# EEZ_AUX_PS_r5B6b.net
KiCad netlist of a schematic drawn in EAGLE
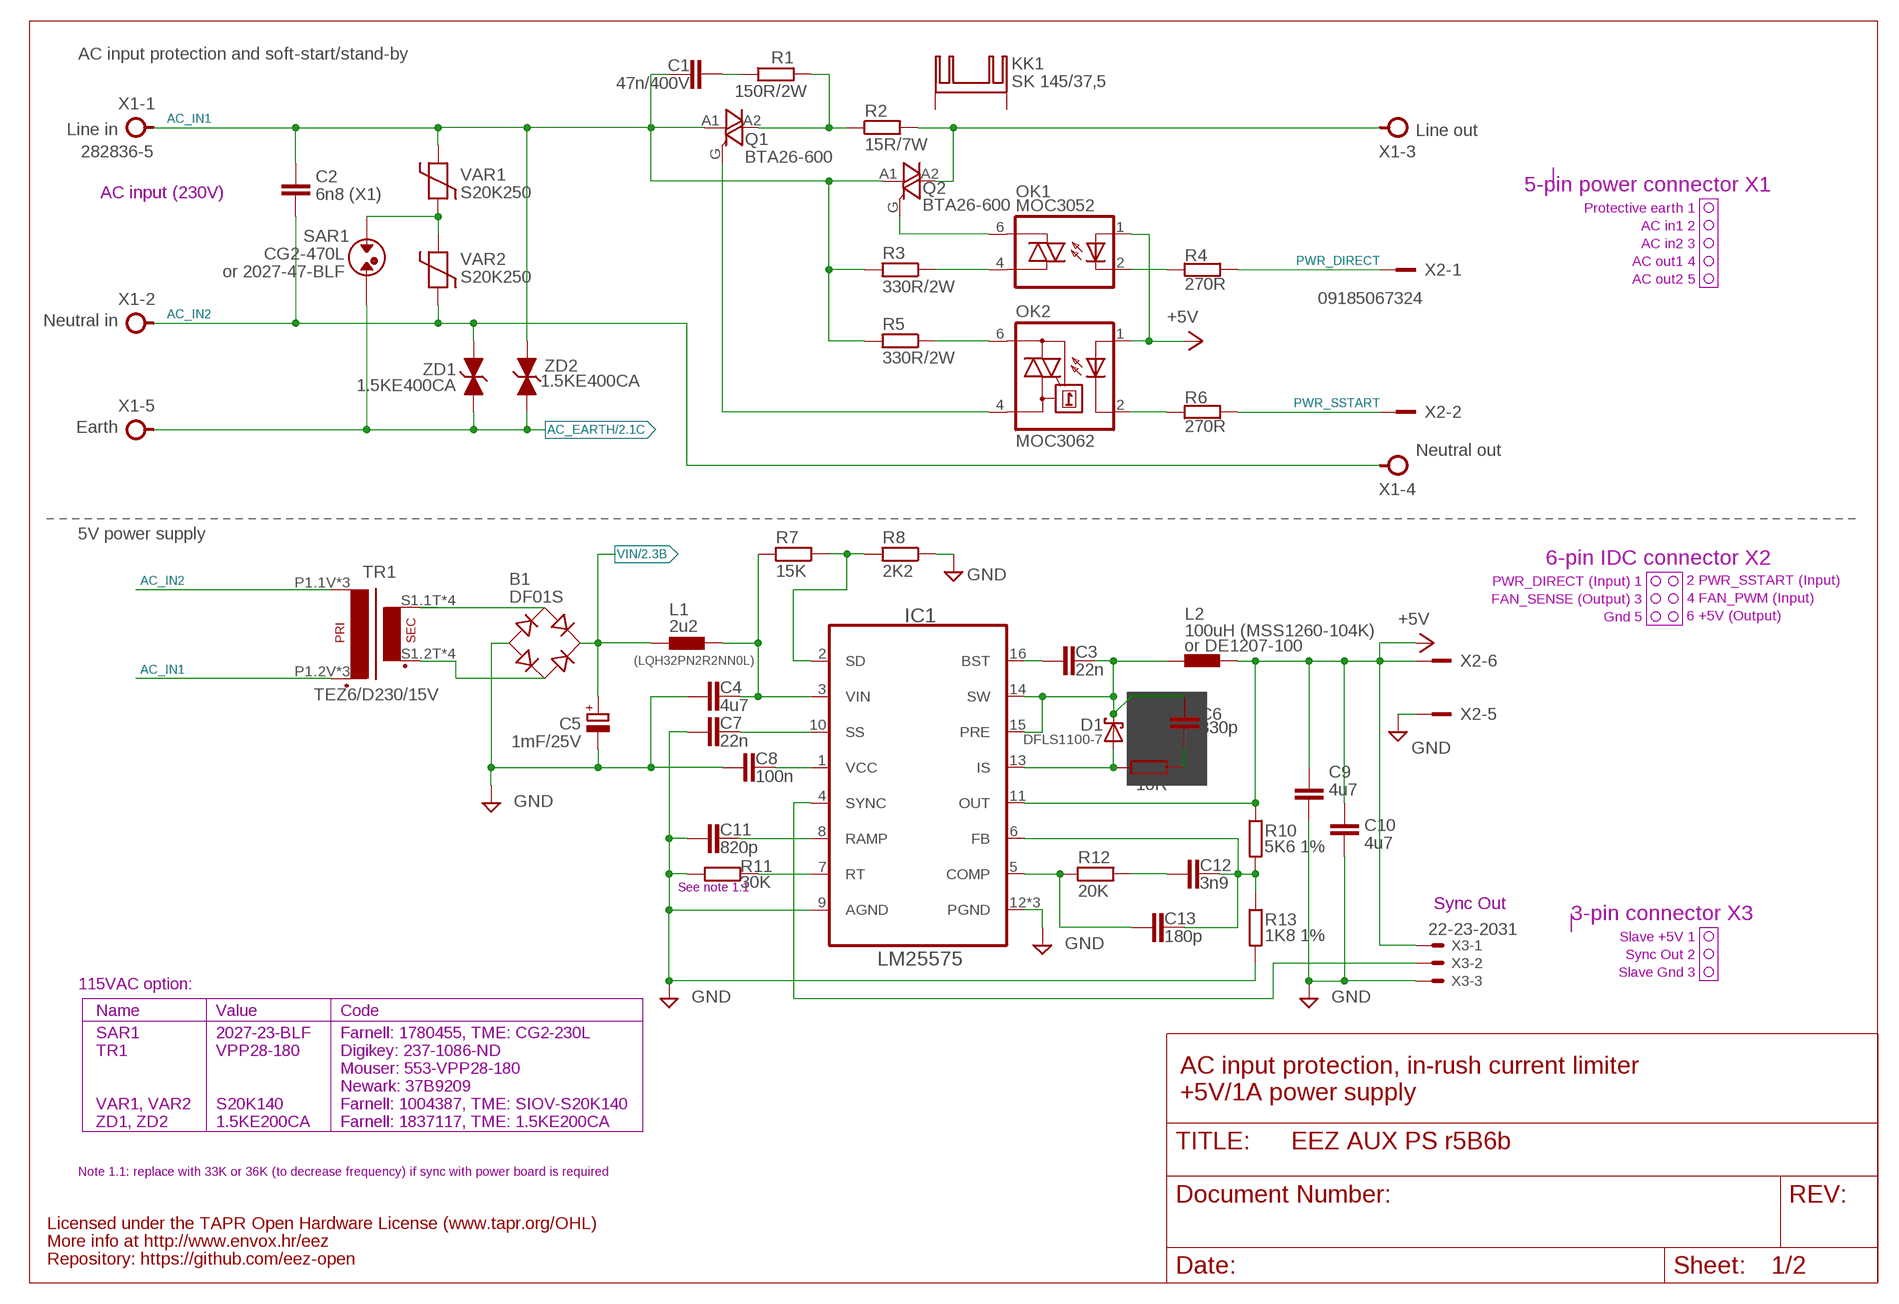
[diagram p0: schematic, sheet 1]
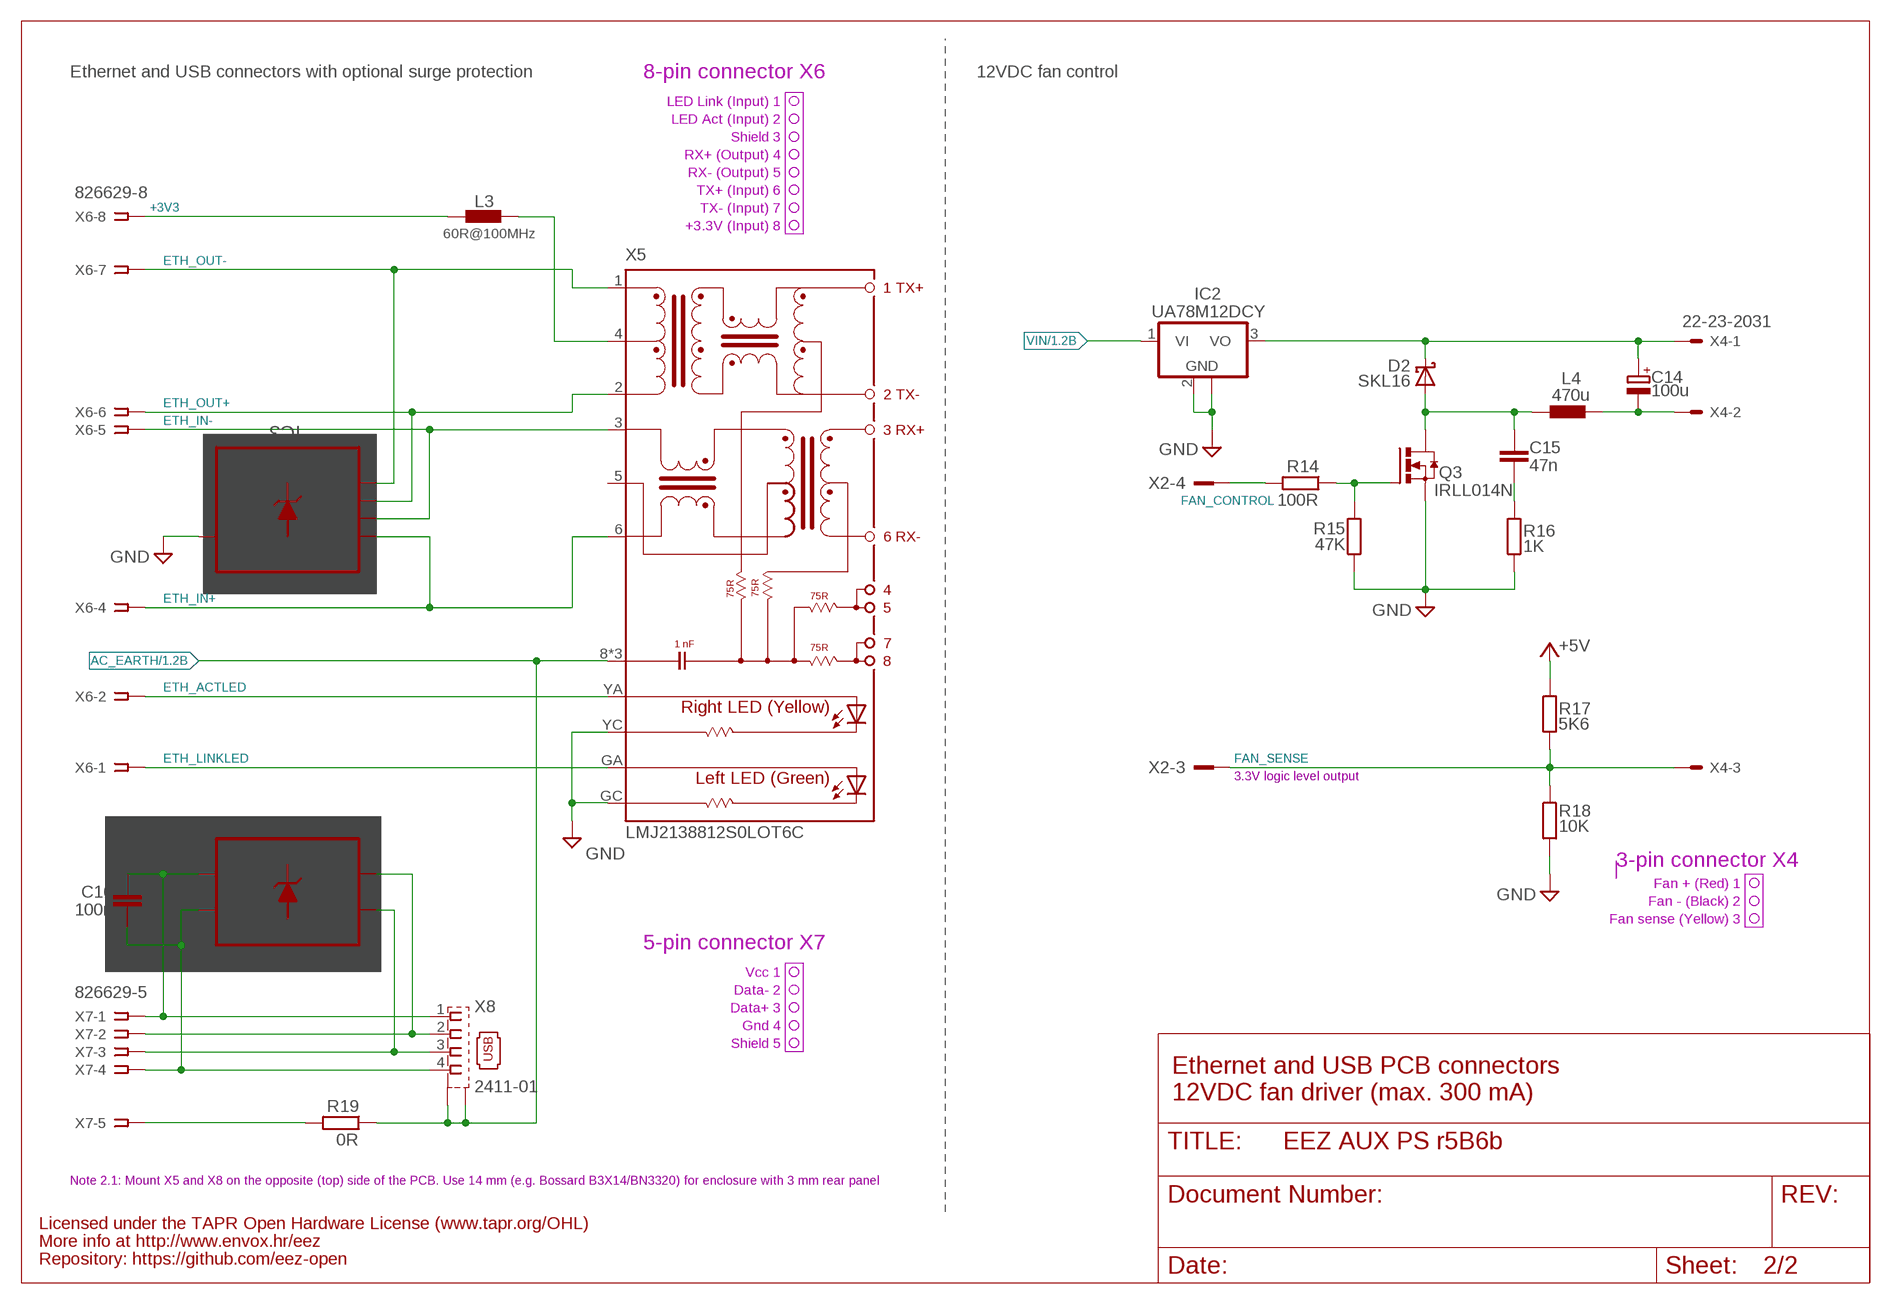
[diagram p1: schematic, sheet 2]

(export (version "E")
  (design (tool "Eeschema 10.0.6"))
  (components
    (comp (ref "C14")
      (value "100u")
      (footprint "eagle-import:CAPAE660X610N")
      (libsource (lib "eagle-import") (part "ECAPPANASONIC_H"))
    )
    (comp (ref "C15")
      (value "47n")
      (footprint "eagle-import:C0805")
      (libsource (lib "eagle-import") (part "C-EUC0805"))
    )
    (comp (ref "C16")
      (value "100n")
      (footprint "eagle-import:C0805")
      (libsource (lib "eagle-import") (part "C-EUC0805"))
    )
    (comp (ref "D2")
      (value "SKL16")
      (footprint "eagle-import:SOD123")
      (libsource (lib "eagle-import") (part "SCHOTTKYSOD123"))
    )
    (comp (ref "IC2")
      (value "UA78M12DCY")
      (footprint "eagle-import:SOT230P700X180-4N")
      (libsource (lib "eagle-import") (part "UA78MDCY"))
    )
    (comp (ref "IC3")
      (value "TPD4E002DRLR")
      (footprint "eagle-import:SOT50P280X60-5N")
      (libsource (lib "eagle-import") (part "TPD4E002DRLR"))
    )
    (comp (ref "IC4")
      (value "TPD2E001DZDR")
      (footprint "eagle-import:SOP192P292X122-4N")
      (libsource (lib "eagle-import") (part "TPD2E001DZDR"))
    )
    (comp (ref "L3")
      (value "60R@100MHz")
      (footprint "eagle-import:BEAD0603")
      (libsource (lib "eagle-import") (part "FERRITE_BEAD0603"))
    )
    (comp (ref "L4")
      (value "470u")
      (footprint "eagle-import:DE0704")
      (libsource (lib "eagle-import") (part "DE0704"))
    )
    (comp (ref "Q3")
      (value "IRLL014N")
      (footprint "eagle-import:SOT223")
      (libsource (lib "eagle-import") (part "N-HEXFET-2D_?-SOT232IRLL014N"))
    )
    (comp (ref "R14")
      (value "100R")
      (footprint "eagle-import:R0805")
      (libsource (lib "eagle-import") (part "R-EU_R0805"))
    )
    (comp (ref "R15")
      (value "47K")
      (footprint "eagle-import:R0805")
      (libsource (lib "eagle-import") (part "R-EU_R0805"))
    )
    (comp (ref "R16")
      (value "1K")
      (footprint "eagle-import:R0805")
      (libsource (lib "eagle-import") (part "R-EU_R0805"))
    )
    (comp (ref "R17")
      (value "5K6")
      (footprint "eagle-import:R0805")
      (libsource (lib "eagle-import") (part "R-EU_R0805"))
    )
    (comp (ref "R18")
      (value "10K")
      (footprint "eagle-import:R0805")
      (libsource (lib "eagle-import") (part "R-EU_R0805"))
    )
    (comp (ref "R19")
      (value "0R")
      (footprint "eagle-import:R0805")
      (libsource (lib "eagle-import") (part "R-EU_R0805"))
    )
    (comp (ref "X2")
      (value "09185067324")
      (footprint "eagle-import:IDC-6PIN")
      (libsource (lib "eagle-import") (part "IDC-6PIN"))
    )
    (comp (ref "X4")
      (value "22-23-2031")
      (footprint "eagle-import:22-23-2031")
      (fields (field (name "MF") "MOLEX"))
      (libsource (lib "eagle-import") (part "22-23-2031"))
    )
    (comp (ref "X5")
      (value "LMJ2138812S0LOT6C")
      (footprint "eagle-import:RJ45-VERT")
      (libsource (lib "eagle-import") (part "RJ45-VERT"))
    )
    (comp (ref "X6")
      (value "826629-8")
      (footprint "eagle-import:SSW-108-02-S-S")
      (fields (field (name "MPN") "SSW-108-02-S-S"))
      (libsource (lib "eagle-import") (part "SSW-108-02-S-S"))
    )
    (comp (ref "X7")
      (value "826629-5")
      (footprint "eagle-import:SSW-105-02-S-S")
      (fields (field (name "MPN") "SSW-105-02-S-S"))
      (libsource (lib "eagle-import") (part "SSW-105-02-S-S"))
    )
    (comp (ref "X8")
      (value "2411-01")
      (footprint "eagle-import:KUSBVX-BS1N")
      (libsource (lib "eagle-import") (part "KUSBVX-BS1N"))
    )
    (comp (ref "B1")
      (value "DF01S")
      (footprint "eagle-import:DFS")
      (libsource (lib "eagle-import") (part "DFS01"))
    )
    (comp (ref "C1")
      (value "47n/400V")
      (footprint "eagle-import:C075-052X106")
      (libsource (lib "eagle-import") (part "C-EU075-052X106"))
    )
    (comp (ref "C2")
      (value "6n8 (X1)")
      (footprint "eagle-import:C102-064X133")
      (libsource (lib "eagle-import") (part "C-EU102-064X133"))
    )
    (comp (ref "C3")
      (value "22n")
      (footprint "eagle-import:C0805")
      (libsource (lib "eagle-import") (part "C-EUC0805"))
    )
    (comp (ref "C4")
      (value "4u7")
      (footprint "eagle-import:C1210")
      (libsource (lib "eagle-import") (part "C-EUC1210"))
    )
    (comp (ref "C5")
      (value "1mF/25V")
      (footprint "eagle-import:ECAP5_10.5")
      (libsource (lib "eagle-import") (part "ECAP5G_10.5MM"))
    )
    (comp (ref "C6")
      (value "330p")
      (footprint "eagle-import:C0805")
      (libsource (lib "eagle-import") (part "C-EUC0805"))
    )
    (comp (ref "C7")
      (value "22n")
      (footprint "eagle-import:C0805")
      (libsource (lib "eagle-import") (part "C-EUC0805"))
    )
    (comp (ref "C8")
      (value "100n")
      (footprint "eagle-import:C0805")
      (libsource (lib "eagle-import") (part "C-EUC0805"))
    )
    (comp (ref "C9")
      (value "4u7")
      (footprint "eagle-import:C1210")
      (libsource (lib "eagle-import") (part "C-EUC1210"))
    )
    (comp (ref "C10")
      (value "4u7")
      (footprint "eagle-import:C1210")
      (libsource (lib "eagle-import") (part "C-EUC1210"))
    )
    (comp (ref "C11")
      (value "820p")
      (footprint "eagle-import:C0805")
      (libsource (lib "eagle-import") (part "C-EUC0805"))
    )
    (comp (ref "C12")
      (value "3n9")
      (footprint "eagle-import:C0805")
      (libsource (lib "eagle-import") (part "C-EUC0805"))
    )
    (comp (ref "C13")
      (value "180p")
      (footprint "eagle-import:C0805")
      (libsource (lib "eagle-import") (part "C-EUC0805"))
    )
    (comp (ref "D1")
      (value "DFLS1100-7")
      (footprint "eagle-import:SOD123")
      (libsource (lib "eagle-import") (part "SCHOTTKYSOD123"))
    )
    (comp (ref "IC1")
      (value "LM25575")
      (footprint "eagle-import:SOP65P640X110-17N_HOLE")
      (libsource (lib "eagle-import") (part "LM(2)5575"))
    )
    (comp (ref "KK1")
      (value "SK 145/37,5")
      (footprint "eagle-import:SK145")
      (libsource (lib "eagle-import") (part "SK145"))
    )
    (comp (ref "L1")
      (value "2u2")
      (footprint "eagle-import:L1210")
      (libsource (lib "eagle-import") (part "L1210"))
    )
    (comp (ref "L2")
      (value "100uH (MSS1260-104K)")
      (footprint "eagle-import:MSS1278")
      (libsource (lib "eagle-import") (part "COILCRAFT_MSS1278"))
    )
    (comp (ref "OK1")
      (value "MOC3052")
      (footprint "eagle-import:DIL6-SMD")
      (libsource (lib "eagle-import") (part "MOC305X"))
    )
    (comp (ref "OK2")
      (value "MOC3062")
      (footprint "eagle-import:DIL6-SMD")
      (fields
        (field (name "MF") "FAIRCHILD SEMICONDUCTOR")
        (field (name "MPN") "MOC3033S-M")
        (field (name "MF_1") "FAIRCHILD SEMICONDUCTOR")
        (field (name "MPN_1") "MOC3033S-M")
        (field (name "OC_FARNELL") "unknown")
        (field (name "OC_NEWARK") "05C2878")
      )
      (libsource (lib "eagle-import") (part "MOC30S33"))
    )
    (comp (ref "Q1")
      (value "BTA26-600")
      (footprint "eagle-import:TOP3S-1")
      (libsource (lib "eagle-import") (part "BTA26-V"))
    )
    (comp (ref "Q2")
      (value "BTA26-600")
      (footprint "eagle-import:TOP3S-1")
      (libsource (lib "eagle-import") (part "BTA26-V"))
    )
    (comp (ref "R1")
      (value "150R/2W")
      (footprint "eagle-import:R2512")
      (libsource (lib "eagle-import") (part "R-EU_R2512"))
    )
    (comp (ref "R2")
      (value "15R/7W")
      (footprint "eagle-import:R_0913")
      (libsource (lib "eagle-import") (part "R_EU7W"))
    )
    (comp (ref "R3")
      (value "330R/2W")
      (footprint "eagle-import:R2512")
      (libsource (lib "eagle-import") (part "R-EU_R2512"))
    )
    (comp (ref "R4")
      (value "270R")
      (footprint "eagle-import:R0805")
      (libsource (lib "eagle-import") (part "R-EU_R0805"))
    )
    (comp (ref "R5")
      (value "330R/2W")
      (footprint "eagle-import:R2512")
      (libsource (lib "eagle-import") (part "R-EU_R2512"))
    )
    (comp (ref "R6")
      (value "270R")
      (footprint "eagle-import:R0805")
      (libsource (lib "eagle-import") (part "R-EU_R0805"))
    )
    (comp (ref "R7")
      (value "15K")
      (footprint "eagle-import:R0805")
      (libsource (lib "eagle-import") (part "R-EU_R0805"))
    )
    (comp (ref "R8")
      (value "2K2")
      (footprint "eagle-import:R0805")
      (libsource (lib "eagle-import") (part "R-EU_R0805"))
    )
    (comp (ref "R9")
      (value "10R")
      (footprint "eagle-import:R1206")
      (libsource (lib "eagle-import") (part "R-EU_R1206"))
    )
    (comp (ref "R10")
      (value "5K6 1%")
      (footprint "eagle-import:R0805")
      (libsource (lib "eagle-import") (part "R-EU_R0805"))
    )
    (comp (ref "R11")
      (value "30K")
      (footprint "eagle-import:R0805")
      (libsource (lib "eagle-import") (part "R-EU_R0805"))
    )
    (comp (ref "R12")
      (value "20K")
      (footprint "eagle-import:R0805")
      (libsource (lib "eagle-import") (part "R-EU_R0805"))
    )
    (comp (ref "R13")
      (value "1K8 1%")
      (footprint "eagle-import:R0805")
      (libsource (lib "eagle-import") (part "R-EU_R0805"))
    )
    (comp (ref "SAR1")
      (value "CG2-470L")
      (footprint "eagle-import:SAR")
      (libsource (lib "eagle-import") (part "SAR"))
    )
    (comp (ref "TR1")
      (value "TEZ6/D230/15V")
      (footprint "eagle-import:PCB_TRAFO6VA_TEZ+VPP")
      (libsource (lib "eagle-import") (part "PCB_TRAFO6VA_TEZ+VPP"))
    )
    (comp (ref "VAR1")
      (value "S20K250")
      (footprint "eagle-import:VARISTOR")
      (libsource (lib "eagle-import") (part "VARISTOR"))
    )
    (comp (ref "VAR2")
      (value "S20K250")
      (footprint "eagle-import:VARISTOR")
      (libsource (lib "eagle-import") (part "VARISTOR"))
    )
    (comp (ref "X1")
      (value "282836-5")
      (footprint "eagle-import:TBLOCK5.0_5")
      (libsource (lib "eagle-import") (part "TBLOCK5.0_5A"))
    )
    (comp (ref "X3")
      (value "22-23-2031")
      (footprint "eagle-import:22-23-2031")
      (fields (field (name "MF") "MOLEX"))
      (libsource (lib "eagle-import") (part "22-23-2031"))
    )
    (comp (ref "ZD1")
      (value "1.5KE400CA")
      (footprint "eagle-import:DO201-BIDIR")
      (libsource (lib "eagle-import") (part "1.5KE-BIDIR"))
    )
    (comp (ref "ZD2")
      (value "1.5KE400CA")
      (footprint "eagle-import:DO201-BIDIR")
      (libsource (lib "eagle-import") (part "1.5KE-BIDIR"))
    )
  )
  (nets
    (net (code "1") (name "+3V3") (class "Default")
      (node (ref "L3") (pin "P$2") (pinfunction "2_P$2") (pintype "passive"))
      (node (ref "X6") (pin "8") (pinfunction "1_8") (pintype "passive"))
    )
    (net (code "2") (name "+5V") (class "Default")
      (node (ref "C10") (pin "1") (pinfunction "1_1") (pintype "passive"))
      (node (ref "C9") (pin "1") (pinfunction "1_1") (pintype "passive"))
      (node (ref "IC1") (pin "11") (pinfunction "OUT_11") (pintype "output"))
      (node (ref "L2") (pin "2") (pinfunction "2_2") (pintype "passive"))
      (node (ref "OK1") (pin "1") (pinfunction "A_1") (pintype "passive"))
      (node (ref "OK2") (pin "1") (pinfunction "A_1") (pintype "passive"))
      (node (ref "R10") (pin "1") (pinfunction "1_1") (pintype "passive"))
      (node (ref "R17") (pin "1") (pinfunction "1_1") (pintype "passive"))
      (node (ref "X2") (pin "6") (pinfunction "1_6") (pintype "passive"))
      (node (ref "X3") (pin "1") (pinfunction "S_1") (pintype "passive"))
    )
    (net (code "3") (name "AC_EARTH") (class "Default")
      (node (ref "R19") (pin "1") (pinfunction "1_1") (pintype "passive"))
      (node (ref "SAR1") (pin "P$2") (pinfunction "P$2_P$2") (pintype "bidirectional"))
      (node (ref "X1") (pin "5") (pinfunction "1_5") (pintype "bidirectional"))
      (node (ref "X5") (pin "8") (pinfunction "SH_8") (pintype "input"))
      (node (ref "X5") (pin "SH1") (pinfunction "SH_SH1") (pintype "input"))
      (node (ref "X5") (pin "SH2") (pinfunction "SH_SH2") (pintype "input"))
      (node (ref "X8") (pin "M1") (pinfunction "S1_M1") (pintype "passive"))
      (node (ref "X8") (pin "M2") (pinfunction "S2_M2") (pintype "passive"))
      (node (ref "ZD1") (pin "C") (pinfunction "1_C") (pintype "passive"))
      (node (ref "ZD2") (pin "C") (pinfunction "1_C") (pintype "passive"))
    )
    (net (code "4") (name "AC_IN1") (class "Default")
      (node (ref "C1") (pin "2") (pinfunction "2_2") (pintype "passive"))
      (node (ref "C2") (pin "1") (pinfunction "1_1") (pintype "passive"))
      (node (ref "Q1") (pin "A1") (pinfunction "A1_A1") (pintype "passive"))
      (node (ref "Q2") (pin "A1") (pinfunction "A1_A1") (pintype "passive"))
      (node (ref "R3") (pin "2") (pinfunction "2_2") (pintype "passive"))
      (node (ref "R5") (pin "2") (pinfunction "2_2") (pintype "passive"))
      (node (ref "TR1") (pin "P1.2V") (pinfunction "P2_P1.2V") (pintype "passive"))
      (node (ref "TR1") (pin "P2.2V") (pinfunction "P2_P2.2V") (pintype "passive"))
      (node (ref "TR1") (pin "P2_TEZ") (pinfunction "P2_P2_TEZ") (pintype "passive"))
      (node (ref "VAR1") (pin "P$2") (pinfunction "P$2_P$2") (pintype "bidirectional"))
      (node (ref "X1") (pin "1") (pinfunction "1_1") (pintype "bidirectional"))
      (node (ref "ZD2") (pin "A") (pinfunction "2_A") (pintype "passive"))
    )
    (net (code "5") (name "AC_IN2") (class "Default")
      (node (ref "C2") (pin "2") (pinfunction "2_2") (pintype "passive"))
      (node (ref "TR1") (pin "P1.1V") (pinfunction "P1_P1.1V") (pintype "passive"))
      (node (ref "TR1") (pin "P1_TEZ") (pinfunction "P1_P1_TEZ") (pintype "passive"))
      (node (ref "TR1") (pin "P2.1V") (pinfunction "P1_P2.1V") (pintype "passive"))
      (node (ref "VAR2") (pin "P$1") (pinfunction "P$1_P$1") (pintype "bidirectional"))
      (node (ref "X1") (pin "2") (pinfunction "1_2") (pintype "bidirectional"))
      (node (ref "X1") (pin "4") (pinfunction "1_4") (pintype "bidirectional"))
      (node (ref "ZD1") (pin "A") (pinfunction "2_A") (pintype "passive"))
    )
    (net (code "6") (name "ETH_ACTLED") (class "Default")
      (node (ref "X5") (pin "YA") (pinfunction "YELLOW_A_YA") (pintype "passive"))
      (node (ref "X6") (pin "2") (pinfunction "1_2") (pintype "passive"))
    )
    (net (code "7") (name "ETH_IN+") (class "Default")
      (node (ref "IC3") (pin "5") (pinfunction "IO4_5") (pintype "bidirectional"))
      (node (ref "X5") (pin "6") (pinfunction "RD-_6") (pintype "input"))
      (node (ref "X6") (pin "4") (pinfunction "1_4") (pintype "passive"))
    )
    (net (code "8") (name "ETH_IN-") (class "Default")
      (node (ref "IC3") (pin "4") (pinfunction "IO3_4") (pintype "bidirectional"))
      (node (ref "X5") (pin "3") (pinfunction "RD+_3") (pintype "input"))
      (node (ref "X6") (pin "5") (pinfunction "1_5") (pintype "passive"))
    )
    (net (code "9") (name "ETH_LINKLED") (class "Default")
      (node (ref "X5") (pin "GA") (pinfunction "GREEN-A_GA") (pintype "passive"))
      (node (ref "X6") (pin "1") (pinfunction "1_1") (pintype "passive"))
    )
    (net (code "10") (name "ETH_OUT+") (class "Default")
      (node (ref "IC3") (pin "3") (pinfunction "IO2_3") (pintype "bidirectional"))
      (node (ref "X5") (pin "2") (pinfunction "TD-_2") (pintype "input"))
      (node (ref "X6") (pin "6") (pinfunction "1_6") (pintype "passive"))
    )
    (net (code "11") (name "ETH_OUT-") (class "Default")
      (node (ref "IC3") (pin "1") (pinfunction "IO1_1") (pintype "bidirectional"))
      (node (ref "X5") (pin "1") (pinfunction "TD+_1") (pintype "input"))
      (node (ref "X6") (pin "7") (pinfunction "1_7") (pintype "passive"))
    )
    (net (code "12") (name "FAN_CONTROL") (class "Default")
      (node (ref "R14") (pin "2") (pinfunction "2_2") (pintype "passive"))
      (node (ref "X2") (pin "4") (pinfunction "1_4") (pintype "passive"))
    )
    (net (code "13") (name "FAN_SENSE") (class "Default")
      (node (ref "R17") (pin "2") (pinfunction "2_2") (pintype "passive"))
      (node (ref "R18") (pin "1") (pinfunction "1_1") (pintype "passive"))
      (node (ref "X2") (pin "3") (pinfunction "1_3") (pintype "passive"))
      (node (ref "X4") (pin "3") (pinfunction "S_3") (pintype "passive"))
    )
    (net (code "14") (name "GND") (class "Default")
      (node (ref "B1") (pin "-") (pinfunction "-_-") (pintype "passive"))
      (node (ref "C10") (pin "2") (pinfunction "2_2") (pintype "passive"))
      (node (ref "C11") (pin "1") (pinfunction "1_1") (pintype "passive"))
      (node (ref "C4") (pin "2") (pinfunction "2_2") (pintype "passive"))
      (node (ref "C5") (pin "-") (pinfunction "-_-") (pintype "passive"))
      (node (ref "C7") (pin "2") (pinfunction "2_2") (pintype "passive"))
      (node (ref "C8") (pin "1") (pinfunction "1_1") (pintype "passive"))
      (node (ref "C9") (pin "2") (pinfunction "2_2") (pintype "passive"))
      (node (ref "IC1") (pin "12") (pinfunction "PGND_12") (pintype "passive"))
      (node (ref "IC1") (pin "9") (pinfunction "AGND_9") (pintype "passive"))
      (node (ref "IC1") (pin "TP") (pinfunction "PGND_TP") (pintype "passive"))
      (node (ref "IC1") (pin "TP2") (pinfunction "PGND_TP2") (pintype "passive"))
      (node (ref "IC2") (pin "2") (pinfunction "GND_2") (pintype "passive"))
      (node (ref "IC2") (pin "4") (pinfunction "GND_4") (pintype "passive"))
      (node (ref "IC3") (pin "2") (pinfunction "GND_2") (pintype "passive"))
      (node (ref "Q3") (pin "3") (pinfunction "S_3") (pintype "passive"))
      (node (ref "R11") (pin "2") (pinfunction "2_2") (pintype "passive"))
      (node (ref "R13") (pin "2") (pinfunction "2_2") (pintype "passive"))
      (node (ref "R15") (pin "1") (pinfunction "1_1") (pintype "passive"))
      (node (ref "R16") (pin "1") (pinfunction "1_1") (pintype "passive"))
      (node (ref "R18") (pin "2") (pinfunction "2_2") (pintype "passive"))
      (node (ref "R8") (pin "1") (pinfunction "1_1") (pintype "passive"))
      (node (ref "X2") (pin "5") (pinfunction "1_5") (pintype "passive"))
      (node (ref "X3") (pin "3") (pinfunction "S_3") (pintype "passive"))
      (node (ref "X5") (pin "GC") (pinfunction "GREEN-C_GC") (pintype "passive"))
      (node (ref "X5") (pin "YC") (pinfunction "YELLOW-C_YC") (pintype "passive"))
    )
    (net (code "15") (name "Net-(B1-PadAC1)") (class "Default")
      (node (ref "B1") (pin "AC1") (pinfunction "AC1_AC1") (pintype "passive"))
      (node (ref "TR1") (pin "S1.1T") (pinfunction "S1_S1.1T") (pintype "passive"))
      (node (ref "TR1") (pin "S1.1V") (pinfunction "S1_S1.1V") (pintype "passive"))
      (node (ref "TR1") (pin "S2.1T") (pinfunction "S1_S2.1T") (pintype "passive"))
      (node (ref "TR1") (pin "S2.1V") (pinfunction "S1_S2.1V") (pintype "passive"))
    )
    (net (code "16") (name "Net-(B1-PadAC2)") (class "Default")
      (node (ref "B1") (pin "AC2") (pinfunction "AC2_AC2") (pintype "passive"))
      (node (ref "TR1") (pin "S1.2T") (pinfunction "S2_S1.2T") (pintype "passive"))
      (node (ref "TR1") (pin "S1.2V") (pinfunction "S2_S1.2V") (pintype "passive"))
      (node (ref "TR1") (pin "S2.2T") (pinfunction "S2_S2.2T") (pintype "passive"))
      (node (ref "TR1") (pin "S2.2V") (pinfunction "S2_S2.2V") (pintype "passive"))
    )
    (net (code "17") (name "Net-(C1-Pad1)") (class "Default")
      (node (ref "C1") (pin "1") (pinfunction "1_1") (pintype "passive"))
      (node (ref "R1") (pin "1") (pinfunction "1_1") (pintype "passive"))
    )
    (net (code "18") (name "Net-(C6-Pad2)") (class "Default")
      (node (ref "C6") (pin "2") (pinfunction "2_2") (pintype "passive"))
      (node (ref "R9") (pin "2") (pinfunction "2_2") (pintype "passive"))
    )
    (net (code "19") (name "Net-(C12-Pad2)") (class "Default")
      (node (ref "C12") (pin "2") (pinfunction "2_2") (pintype "passive"))
      (node (ref "R12") (pin "2") (pinfunction "2_2") (pintype "passive"))
    )
    (net (code "20") (name "Net-(C14-+)") (class "Default")
      (node (ref "C14") (pin "1") (pinfunction "+_1") (pintype "passive"))
      (node (ref "D2") (pin "C") (pinfunction "C_C") (pintype "passive"))
      (node (ref "IC2") (pin "3") (pinfunction "VO_3") (pintype "passive"))
      (node (ref "X4") (pin "1") (pinfunction "S_1") (pintype "passive"))
    )
    (net (code "21") (name "Net-(C14--)") (class "Default")
      (node (ref "C14") (pin "2") (pinfunction "-_2") (pintype "passive"))
      (node (ref "L4") (pin "1") (pinfunction "1_1") (pintype "passive"))
      (node (ref "X4") (pin "2") (pinfunction "S_2") (pintype "passive"))
    )
    (net (code "22") (name "Net-(C15-Pad1)") (class "Default")
      (node (ref "C15") (pin "1") (pinfunction "1_1") (pintype "passive"))
      (node (ref "R16") (pin "2") (pinfunction "2_2") (pintype "passive"))
    )
    (net (code "23") (name "Net-(C15-Pad2)") (class "Default")
      (node (ref "C15") (pin "2") (pinfunction "2_2") (pintype "passive"))
      (node (ref "D2") (pin "A") (pinfunction "A_A") (pintype "passive"))
      (node (ref "L4") (pin "2") (pinfunction "2_2") (pintype "passive"))
      (node (ref "Q3") (pin "2") (pinfunction "D_2") (pintype "passive"))
      (node (ref "Q3") (pin "4") (pinfunction "D_4") (pintype "passive"))
    )
    (net (code "24") (name "Net-(IC1-BST)") (class "Default")
      (node (ref "C3") (pin "2") (pinfunction "2_2") (pintype "passive"))
      (node (ref "IC1") (pin "16") (pinfunction "BST_16") (pintype "input"))
    )
    (net (code "25") (name "Net-(IC1-COMP)") (class "Default")
      (node (ref "C13") (pin "2") (pinfunction "2_2") (pintype "passive"))
      (node (ref "IC1") (pin "5") (pinfunction "COMP_5") (pintype "input"))
      (node (ref "R12") (pin "1") (pinfunction "1_1") (pintype "passive"))
    )
    (net (code "26") (name "Net-(IC1-FB)") (class "Default")
      (node (ref "C12") (pin "1") (pinfunction "1_1") (pintype "passive"))
      (node (ref "C13") (pin "1") (pinfunction "1_1") (pintype "passive"))
      (node (ref "IC1") (pin "6") (pinfunction "FB_6") (pintype "input"))
      (node (ref "R10") (pin "2") (pinfunction "2_2") (pintype "passive"))
      (node (ref "R13") (pin "1") (pinfunction "1_1") (pintype "passive"))
    )
    (net (code "27") (name "Net-(IC1-IS)") (class "Default")
      (node (ref "D1") (pin "A") (pinfunction "A_A") (pintype "passive"))
      (node (ref "IC1") (pin "13") (pinfunction "IS_13") (pintype "input"))
      (node (ref "R9") (pin "1") (pinfunction "1_1") (pintype "passive"))
    )
    (net (code "28") (name "Net-(IC1-PRE)") (class "Default")
      (node (ref "C3") (pin "1") (pinfunction "1_1") (pintype "passive"))
      (node (ref "C6") (pin "1") (pinfunction "1_1") (pintype "passive"))
      (node (ref "D1") (pin "C") (pinfunction "C_C") (pintype "passive"))
      (node (ref "IC1") (pin "14") (pinfunction "SW_14") (pintype "output"))
      (node (ref "IC1") (pin "15") (pinfunction "PRE_15") (pintype "input"))
      (node (ref "L2") (pin "1") (pinfunction "1_1") (pintype "passive"))
    )
    (net (code "29") (name "Net-(IC1-RAMP)") (class "Default")
      (node (ref "C11") (pin "2") (pinfunction "2_2") (pintype "passive"))
      (node (ref "IC1") (pin "8") (pinfunction "RAMP_8") (pintype "input"))
    )
    (net (code "30") (name "Net-(IC1-RT)") (class "Default")
      (node (ref "IC1") (pin "7") (pinfunction "RT_7") (pintype "input"))
      (node (ref "R11") (pin "1") (pinfunction "1_1") (pintype "passive"))
    )
    (net (code "31") (name "Net-(IC1-SD)") (class "Default")
      (node (ref "IC1") (pin "2") (pinfunction "SD_2") (pintype "input"))
      (node (ref "R7") (pin "1") (pinfunction "1_1") (pintype "passive"))
      (node (ref "R8") (pin "2") (pinfunction "2_2") (pintype "passive"))
    )
    (net (code "32") (name "Net-(IC1-SS)") (class "Default")
      (node (ref "C7") (pin "1") (pinfunction "1_1") (pintype "passive"))
      (node (ref "IC1") (pin "10") (pinfunction "SS_10") (pintype "input"))
    )
    (net (code "33") (name "Net-(IC1-SYNC)") (class "Default")
      (node (ref "IC1") (pin "4") (pinfunction "SYNC_4") (pintype "input"))
      (node (ref "X3") (pin "2") (pinfunction "S_2") (pintype "passive"))
    )
    (net (code "34") (name "Net-(IC1-VCC)") (class "Default")
      (node (ref "C8") (pin "2") (pinfunction "2_2") (pintype "passive"))
      (node (ref "IC1") (pin "1") (pinfunction "VCC_1") (pintype "power_in"))
    )
    (net (code "35") (name "Net-(IC1-VIN)") (class "Default")
      (node (ref "C4") (pin "1") (pinfunction "1_1") (pintype "passive"))
      (node (ref "IC1") (pin "3") (pinfunction "VIN_3") (pintype "input"))
      (node (ref "L1") (pin "2") (pinfunction "2_2") (pintype "passive"))
      (node (ref "R7") (pin "2") (pinfunction "2_2") (pintype "passive"))
    )
    (net (code "36") (name "Net-(IC4-GND)") (class "Default")
      (node (ref "C16") (pin "1") (pinfunction "1_1") (pintype "passive"))
      (node (ref "IC4") (pin "1") (pinfunction "GND_1") (pintype "passive"))
      (node (ref "X7") (pin "4") (pinfunction "1_4") (pintype "passive"))
      (node (ref "X8") (pin "4") (pinfunction "4_4") (pintype "passive"))
    )
    (net (code "37") (name "Net-(IC4-IO1)") (class "Default")
      (node (ref "IC4") (pin "2") (pinfunction "IO1_2") (pintype "bidirectional"))
      (node (ref "X7") (pin "2") (pinfunction "1_2") (pintype "passive"))
      (node (ref "X8") (pin "2") (pinfunction "2_2") (pintype "passive"))
    )
    (net (code "38") (name "Net-(IC4-IO2)") (class "Default")
      (node (ref "IC4") (pin "3") (pinfunction "IO2_3") (pintype "bidirectional"))
      (node (ref "X7") (pin "3") (pinfunction "1_3") (pintype "passive"))
      (node (ref "X8") (pin "3") (pinfunction "3_3") (pintype "passive"))
    )
    (net (code "39") (name "Net-(IC4-VCC)") (class "Default")
      (node (ref "C16") (pin "2") (pinfunction "2_2") (pintype "passive"))
      (node (ref "IC4") (pin "4") (pinfunction "VCC_4") (pintype "power_in"))
      (node (ref "X7") (pin "1") (pinfunction "1_1") (pintype "passive"))
      (node (ref "X8") (pin "1") (pinfunction "1_1") (pintype "passive"))
    )
    (net (code "40") (name "Net-(L3-1)") (class "Default")
      (node (ref "L3") (pin "P$1") (pinfunction "1_P$1") (pintype "passive"))
      (node (ref "X5") (pin "4") (pinfunction "CT_4") (pintype "input"))
    )
    (net (code "41") (name "Net-(OK1-A1)") (class "Default")
      (node (ref "OK1") (pin "4") (pinfunction "A1_4") (pintype "passive"))
      (node (ref "R3") (pin "1") (pinfunction "1_1") (pintype "passive"))
    )
    (net (code "42") (name "Net-(OK1-A2)") (class "Default")
      (node (ref "OK1") (pin "6") (pinfunction "A2_6") (pintype "passive"))
      (node (ref "Q2") (pin "G") (pinfunction "G_G") (pintype "passive"))
    )
    (net (code "43") (name "Net-(OK1-C)") (class "Default")
      (node (ref "OK1") (pin "2") (pinfunction "C_2") (pintype "passive"))
      (node (ref "R4") (pin "1") (pinfunction "1_1") (pintype "passive"))
    )
    (net (code "44") (name "Net-(OK2-A1)") (class "Default")
      (node (ref "OK2") (pin "4") (pinfunction "A1_4") (pintype "passive"))
      (node (ref "Q1") (pin "G") (pinfunction "G_G") (pintype "passive"))
    )
    (net (code "45") (name "Net-(OK2-A2)") (class "Default")
      (node (ref "OK2") (pin "6") (pinfunction "A2_6") (pintype "passive"))
      (node (ref "R5") (pin "1") (pinfunction "1_1") (pintype "passive"))
    )
    (net (code "46") (name "Net-(OK2-C)") (class "Default")
      (node (ref "OK2") (pin "2") (pinfunction "C_2") (pintype "passive"))
      (node (ref "R6") (pin "1") (pinfunction "1_1") (pintype "passive"))
    )
    (net (code "47") (name "Net-(Q1-PadA2)") (class "Default")
      (node (ref "Q1") (pin "A2") (pinfunction "A2_A2") (pintype "passive"))
      (node (ref "R1") (pin "2") (pinfunction "2_2") (pintype "passive"))
      (node (ref "R2") (pin "1") (pinfunction "1_1") (pintype "passive"))
    )
    (net (code "48") (name "Net-(Q3-G)") (class "Default")
      (node (ref "Q3") (pin "1") (pinfunction "G_1") (pintype "passive"))
      (node (ref "R14") (pin "1") (pinfunction "1_1") (pintype "passive"))
      (node (ref "R15") (pin "2") (pinfunction "2_2") (pintype "passive"))
    )
    (net (code "49") (name "Net-(SAR1-PadP$1)") (class "Default")
      (node (ref "SAR1") (pin "P$1") (pinfunction "P$1_P$1") (pintype "bidirectional"))
      (node (ref "VAR1") (pin "P$1") (pinfunction "P$1_P$1") (pintype "bidirectional"))
      (node (ref "VAR2") (pin "P$2") (pinfunction "P$2_P$2") (pintype "bidirectional"))
    )
    (net (code "50") (name "Net-(X1C-1)") (class "Default")
      (node (ref "Q2") (pin "A2") (pinfunction "A2_A2") (pintype "passive"))
      (node (ref "R2") (pin "2") (pinfunction "2_2") (pintype "passive"))
      (node (ref "X1") (pin "3") (pinfunction "1_3") (pintype "bidirectional"))
    )
    (net (code "51") (name "Net-(X7E-1)") (class "Default")
      (node (ref "R19") (pin "2") (pinfunction "2_2") (pintype "passive"))
      (node (ref "X7") (pin "5") (pinfunction "1_5") (pintype "passive"))
    )
    (net (code "52") (name "PWR_DIRECT") (class "Default")
      (node (ref "R4") (pin "2") (pinfunction "2_2") (pintype "passive"))
      (node (ref "X2") (pin "1") (pinfunction "1_1") (pintype "passive"))
    )
    (net (code "53") (name "PWR_SSTART") (class "Default")
      (node (ref "R6") (pin "2") (pinfunction "2_2") (pintype "passive"))
      (node (ref "X2") (pin "2") (pinfunction "1_2") (pintype "passive"))
    )
    (net (code "54") (name "VIN") (class "Default")
      (node (ref "B1") (pin "+") (pinfunction "+_+") (pintype "passive"))
      (node (ref "C5") (pin "+") (pinfunction "+_+") (pintype "passive"))
      (node (ref "IC2") (pin "1") (pinfunction "VI_1") (pintype "input"))
      (node (ref "L1") (pin "1") (pinfunction "1_1") (pintype "passive"))
    )
    (net (code "55") (name "unconnected-(KK1-K-Pad1)") (class "Default")
      (node (ref "KK1") (pin "1") (pinfunction "K_1") (pintype "passive"))
    )
    (net (code "56") (name "unconnected-(KK1-K-Pad2)") (class "Default")
      (node (ref "KK1") (pin "2") (pinfunction "K_2") (pintype "passive"))
    )
    (net (code "57") (name "unconnected-(X5-CR-Pad5)") (class "Default")
      (node (ref "X5") (pin "5") (pinfunction "CR_5") (pintype "input"))
    )
  )
)
